# GIfBoardV3.net
KiCad netlist of a schematic drawn in EAGLE
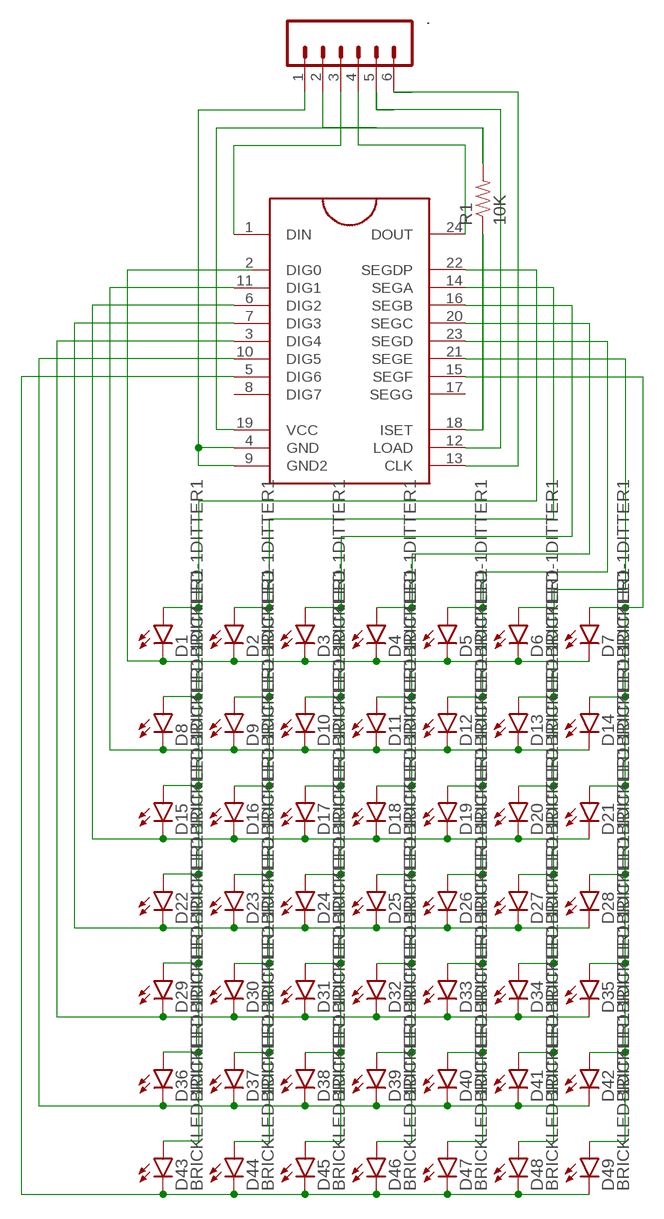
[diagram p0: schematic, sheet 1]

(export (version "E")
  (design (tool "Eeschema 10.0.6"))
  (components
    (comp (ref ".")
      (value "M06NO_SILK_FEMALE_PTH")
      (footprint "eagle-import:1X06_NO_SILK")
      (libsource (lib "eagle-import") (part "M06NO_SILK_FEMALE_PTH"))
    )
    (comp (ref "D1")
      (value "BRICKLED-1DITTER1")
      (footprint "eagle-import:BRICKLED-1DITTER")
      (libsource (lib "eagle-import") (part "BRICKLED-1DITTER1"))
    )
    (comp (ref "D2")
      (value "BRICKLED-1DITTER1")
      (footprint "eagle-import:BRICKLED-1DITTER")
      (libsource (lib "eagle-import") (part "BRICKLED-1DITTER1"))
    )
    (comp (ref "D3")
      (value "BRICKLED-1DITTER1")
      (footprint "eagle-import:BRICKLED-1DITTER")
      (libsource (lib "eagle-import") (part "BRICKLED-1DITTER1"))
    )
    (comp (ref "D4")
      (value "BRICKLED-1DITTER1")
      (footprint "eagle-import:BRICKLED-1DITTER")
      (libsource (lib "eagle-import") (part "BRICKLED-1DITTER1"))
    )
    (comp (ref "D5")
      (value "BRICKLED-1DITTER1")
      (footprint "eagle-import:BRICKLED-1DITTER")
      (libsource (lib "eagle-import") (part "BRICKLED-1DITTER1"))
    )
    (comp (ref "D6")
      (value "BRICKLED-1DITTER1")
      (footprint "eagle-import:BRICKLED-1DITTER")
      (libsource (lib "eagle-import") (part "BRICKLED-1DITTER1"))
    )
    (comp (ref "D7")
      (value "BRICKLED-1DITTER1")
      (footprint "eagle-import:BRICKLED-1DITTER")
      (libsource (lib "eagle-import") (part "BRICKLED-1DITTER1"))
    )
    (comp (ref "D8")
      (value "BRICKLED-1DITTER1")
      (footprint "eagle-import:BRICKLED-1DITTER")
      (libsource (lib "eagle-import") (part "BRICKLED-1DITTER1"))
    )
    (comp (ref "D9")
      (value "BRICKLED-1DITTER1")
      (footprint "eagle-import:BRICKLED-1DITTER")
      (libsource (lib "eagle-import") (part "BRICKLED-1DITTER1"))
    )
    (comp (ref "D10")
      (value "BRICKLED-1DITTER1")
      (footprint "eagle-import:BRICKLED-1DITTER")
      (libsource (lib "eagle-import") (part "BRICKLED-1DITTER1"))
    )
    (comp (ref "D11")
      (value "BRICKLED-1DITTER1")
      (footprint "eagle-import:BRICKLED-1DITTER")
      (libsource (lib "eagle-import") (part "BRICKLED-1DITTER1"))
    )
    (comp (ref "D12")
      (value "BRICKLED-1DITTER1")
      (footprint "eagle-import:BRICKLED-1DITTER")
      (libsource (lib "eagle-import") (part "BRICKLED-1DITTER1"))
    )
    (comp (ref "D13")
      (value "BRICKLED-1DITTER1")
      (footprint "eagle-import:BRICKLED-1DITTER")
      (libsource (lib "eagle-import") (part "BRICKLED-1DITTER1"))
    )
    (comp (ref "D14")
      (value "BRICKLED-1DITTER1")
      (footprint "eagle-import:BRICKLED-1DITTER")
      (libsource (lib "eagle-import") (part "BRICKLED-1DITTER1"))
    )
    (comp (ref "D15")
      (value "BRICKLED-1DITTER1")
      (footprint "eagle-import:BRICKLED-1DITTER")
      (libsource (lib "eagle-import") (part "BRICKLED-1DITTER1"))
    )
    (comp (ref "D16")
      (value "BRICKLED-1DITTER1")
      (footprint "eagle-import:BRICKLED-1DITTER")
      (libsource (lib "eagle-import") (part "BRICKLED-1DITTER1"))
    )
    (comp (ref "D17")
      (value "BRICKLED-1DITTER1")
      (footprint "eagle-import:BRICKLED-1DITTER")
      (libsource (lib "eagle-import") (part "BRICKLED-1DITTER1"))
    )
    (comp (ref "D18")
      (value "BRICKLED-1DITTER1")
      (footprint "eagle-import:BRICKLED-1DITTER")
      (libsource (lib "eagle-import") (part "BRICKLED-1DITTER1"))
    )
    (comp (ref "D19")
      (value "BRICKLED-1DITTER1")
      (footprint "eagle-import:BRICKLED-1DITTER")
      (libsource (lib "eagle-import") (part "BRICKLED-1DITTER1"))
    )
    (comp (ref "D20")
      (value "BRICKLED-1DITTER1")
      (footprint "eagle-import:BRICKLED-1DITTER")
      (libsource (lib "eagle-import") (part "BRICKLED-1DITTER1"))
    )
    (comp (ref "D21")
      (value "BRICKLED-1DITTER1")
      (footprint "eagle-import:BRICKLED-1DITTER")
      (libsource (lib "eagle-import") (part "BRICKLED-1DITTER1"))
    )
    (comp (ref "D22")
      (value "BRICKLED-1DITTER1")
      (footprint "eagle-import:BRICKLED-1DITTER")
      (libsource (lib "eagle-import") (part "BRICKLED-1DITTER1"))
    )
    (comp (ref "D23")
      (value "BRICKLED-1DITTER1")
      (footprint "eagle-import:BRICKLED-1DITTER")
      (libsource (lib "eagle-import") (part "BRICKLED-1DITTER1"))
    )
    (comp (ref "D24")
      (value "BRICKLED-1DITTER1")
      (footprint "eagle-import:BRICKLED-1DITTER")
      (libsource (lib "eagle-import") (part "BRICKLED-1DITTER1"))
    )
    (comp (ref "D25")
      (value "BRICKLED-1DITTER1")
      (footprint "eagle-import:BRICKLED-1DITTER")
      (libsource (lib "eagle-import") (part "BRICKLED-1DITTER1"))
    )
    (comp (ref "D26")
      (value "BRICKLED-1DITTER1")
      (footprint "eagle-import:BRICKLED-1DITTER")
      (libsource (lib "eagle-import") (part "BRICKLED-1DITTER1"))
    )
    (comp (ref "D27")
      (value "BRICKLED-1DITTER1")
      (footprint "eagle-import:BRICKLED-1DITTER")
      (libsource (lib "eagle-import") (part "BRICKLED-1DITTER1"))
    )
    (comp (ref "D28")
      (value "BRICKLED-1DITTER1")
      (footprint "eagle-import:BRICKLED-1DITTER")
      (libsource (lib "eagle-import") (part "BRICKLED-1DITTER1"))
    )
    (comp (ref "D29")
      (value "BRICKLED-1DITTER1")
      (footprint "eagle-import:BRICKLED-1DITTER")
      (libsource (lib "eagle-import") (part "BRICKLED-1DITTER1"))
    )
    (comp (ref "D30")
      (value "BRICKLED-1DITTER1")
      (footprint "eagle-import:BRICKLED-1DITTER")
      (libsource (lib "eagle-import") (part "BRICKLED-1DITTER1"))
    )
    (comp (ref "D31")
      (value "BRICKLED-1DITTER1")
      (footprint "eagle-import:BRICKLED-1DITTER")
      (libsource (lib "eagle-import") (part "BRICKLED-1DITTER1"))
    )
    (comp (ref "D32")
      (value "BRICKLED-1DITTER1")
      (footprint "eagle-import:BRICKLED-1DITTER")
      (libsource (lib "eagle-import") (part "BRICKLED-1DITTER1"))
    )
    (comp (ref "D33")
      (value "BRICKLED-1DITTER1")
      (footprint "eagle-import:BRICKLED-1DITTER")
      (libsource (lib "eagle-import") (part "BRICKLED-1DITTER1"))
    )
    (comp (ref "D34")
      (value "BRICKLED-1DITTER1")
      (footprint "eagle-import:BRICKLED-1DITTER")
      (libsource (lib "eagle-import") (part "BRICKLED-1DITTER1"))
    )
    (comp (ref "D35")
      (value "BRICKLED-1DITTER1")
      (footprint "eagle-import:BRICKLED-1DITTER")
      (libsource (lib "eagle-import") (part "BRICKLED-1DITTER1"))
    )
    (comp (ref "D36")
      (value "BRICKLED-1DITTER1")
      (footprint "eagle-import:BRICKLED-1DITTER")
      (libsource (lib "eagle-import") (part "BRICKLED-1DITTER1"))
    )
    (comp (ref "D37")
      (value "BRICKLED-1DITTER1")
      (footprint "eagle-import:BRICKLED-1DITTER")
      (libsource (lib "eagle-import") (part "BRICKLED-1DITTER1"))
    )
    (comp (ref "D38")
      (value "BRICKLED-1DITTER1")
      (footprint "eagle-import:BRICKLED-1DITTER")
      (libsource (lib "eagle-import") (part "BRICKLED-1DITTER1"))
    )
    (comp (ref "D39")
      (value "BRICKLED-1DITTER1")
      (footprint "eagle-import:BRICKLED-1DITTER")
      (libsource (lib "eagle-import") (part "BRICKLED-1DITTER1"))
    )
    (comp (ref "D40")
      (value "BRICKLED-1DITTER1")
      (footprint "eagle-import:BRICKLED-1DITTER")
      (libsource (lib "eagle-import") (part "BRICKLED-1DITTER1"))
    )
    (comp (ref "D41")
      (value "BRICKLED-1DITTER1")
      (footprint "eagle-import:BRICKLED-1DITTER")
      (libsource (lib "eagle-import") (part "BRICKLED-1DITTER1"))
    )
    (comp (ref "D42")
      (value "BRICKLED-1DITTER1")
      (footprint "eagle-import:BRICKLED-1DITTER")
      (libsource (lib "eagle-import") (part "BRICKLED-1DITTER1"))
    )
    (comp (ref "D43")
      (value "BRICKLED-1DITTER1")
      (footprint "eagle-import:BRICKLED-1DITTER")
      (libsource (lib "eagle-import") (part "BRICKLED-1DITTER1"))
    )
    (comp (ref "D44")
      (value "BRICKLED-1DITTER1")
      (footprint "eagle-import:BRICKLED-1DITTER")
      (libsource (lib "eagle-import") (part "BRICKLED-1DITTER1"))
    )
    (comp (ref "D45")
      (value "BRICKLED-1DITTER1")
      (footprint "eagle-import:BRICKLED-1DITTER")
      (libsource (lib "eagle-import") (part "BRICKLED-1DITTER1"))
    )
    (comp (ref "D46")
      (value "BRICKLED-1DITTER1")
      (footprint "eagle-import:BRICKLED-1DITTER")
      (libsource (lib "eagle-import") (part "BRICKLED-1DITTER1"))
    )
    (comp (ref "D47")
      (value "BRICKLED-1DITTER1")
      (footprint "eagle-import:BRICKLED-1DITTER")
      (libsource (lib "eagle-import") (part "BRICKLED-1DITTER1"))
    )
    (comp (ref "D48")
      (value "BRICKLED-1DITTER1")
      (footprint "eagle-import:BRICKLED-1DITTER")
      (libsource (lib "eagle-import") (part "BRICKLED-1DITTER1"))
    )
    (comp (ref "D49")
      (value "BRICKLED-1DITTER1")
      (footprint "eagle-import:BRICKLED-1DITTER")
      (libsource (lib "eagle-import") (part "BRICKLED-1DITTER1"))
    )
    (comp (ref "MAX7219")
      (value "MAX7219DIP")
      (footprint "eagle-import:DIL24")
      (libsource (lib "eagle-import") (part "MAX7219DIP"))
    )
    (comp (ref "R1")
      (value "10K")
      (footprint "eagle-import:AXIAL-0.3")
      (libsource (lib "eagle-import") (part "1KOHM-1/4W-5%(PTH)"))
    )
  )
  (nets
    (net (code "1") (name "Net-(D1-C)") (class "Default")
      (node (ref "D1") (pin "K") (pinfunction "C_K") (pintype "passive"))
      (node (ref "D2") (pin "K") (pinfunction "C_K") (pintype "passive"))
      (node (ref "D3") (pin "K") (pinfunction "C_K") (pintype "passive"))
      (node (ref "D4") (pin "K") (pinfunction "C_K") (pintype "passive"))
      (node (ref "D5") (pin "K") (pinfunction "C_K") (pintype "passive"))
      (node (ref "D6") (pin "K") (pinfunction "C_K") (pintype "passive"))
      (node (ref "D7") (pin "K") (pinfunction "C_K") (pintype "passive"))
    )
    (net (code "2") (name "Net-(D10-C)") (class "Default")
      (node (ref "D10") (pin "K") (pinfunction "C_K") (pintype "passive"))
      (node (ref "D11") (pin "K") (pinfunction "C_K") (pintype "passive"))
      (node (ref "D12") (pin "K") (pinfunction "C_K") (pintype "passive"))
      (node (ref "D13") (pin "K") (pinfunction "C_K") (pintype "passive"))
      (node (ref "D14") (pin "K") (pinfunction "C_K") (pintype "passive"))
      (node (ref "D8") (pin "K") (pinfunction "C_K") (pintype "passive"))
      (node (ref "D9") (pin "K") (pinfunction "C_K") (pintype "passive"))
      (node (ref "MAX7219") (pin "11") (pinfunction "DIG1_11") (pintype "bidirectional"))
    )
    (net (code "3") (name "Net-(D15-C)") (class "Default")
      (node (ref "D15") (pin "K") (pinfunction "C_K") (pintype "passive"))
      (node (ref "D16") (pin "K") (pinfunction "C_K") (pintype "passive"))
      (node (ref "D17") (pin "K") (pinfunction "C_K") (pintype "passive"))
      (node (ref "D18") (pin "K") (pinfunction "C_K") (pintype "passive"))
      (node (ref "D19") (pin "K") (pinfunction "C_K") (pintype "passive"))
      (node (ref "D20") (pin "K") (pinfunction "C_K") (pintype "passive"))
      (node (ref "D21") (pin "K") (pinfunction "C_K") (pintype "passive"))
      (node (ref "MAX7219") (pin "6") (pinfunction "DIG2_6") (pintype "bidirectional"))
    )
    (net (code "4") (name "Net-(D22-C)") (class "Default")
      (node (ref "D22") (pin "K") (pinfunction "C_K") (pintype "passive"))
      (node (ref "D23") (pin "K") (pinfunction "C_K") (pintype "passive"))
      (node (ref "D24") (pin "K") (pinfunction "C_K") (pintype "passive"))
      (node (ref "D25") (pin "K") (pinfunction "C_K") (pintype "passive"))
      (node (ref "D26") (pin "K") (pinfunction "C_K") (pintype "passive"))
      (node (ref "D27") (pin "K") (pinfunction "C_K") (pintype "passive"))
      (node (ref "D28") (pin "K") (pinfunction "C_K") (pintype "passive"))
      (node (ref "MAX7219") (pin "7") (pinfunction "DIG3_7") (pintype "bidirectional"))
    )
    (net (code "5") (name "Net-(D29-C)") (class "Default")
      (node (ref "D29") (pin "K") (pinfunction "C_K") (pintype "passive"))
      (node (ref "D30") (pin "K") (pinfunction "C_K") (pintype "passive"))
      (node (ref "D31") (pin "K") (pinfunction "C_K") (pintype "passive"))
      (node (ref "D32") (pin "K") (pinfunction "C_K") (pintype "passive"))
      (node (ref "D33") (pin "K") (pinfunction "C_K") (pintype "passive"))
      (node (ref "D34") (pin "K") (pinfunction "C_K") (pintype "passive"))
      (node (ref "D35") (pin "K") (pinfunction "C_K") (pintype "passive"))
      (node (ref "MAX7219") (pin "3") (pinfunction "DIG4_3") (pintype "bidirectional"))
    )
    (net (code "6") (name "Net-(D36-C)") (class "Default")
      (node (ref "D36") (pin "K") (pinfunction "C_K") (pintype "passive"))
      (node (ref "D37") (pin "K") (pinfunction "C_K") (pintype "passive"))
      (node (ref "D38") (pin "K") (pinfunction "C_K") (pintype "passive"))
      (node (ref "D39") (pin "K") (pinfunction "C_K") (pintype "passive"))
      (node (ref "D40") (pin "K") (pinfunction "C_K") (pintype "passive"))
      (node (ref "D41") (pin "K") (pinfunction "C_K") (pintype "passive"))
      (node (ref "D42") (pin "K") (pinfunction "C_K") (pintype "passive"))
      (node (ref "MAX7219") (pin "10") (pinfunction "DIG5_10") (pintype "bidirectional"))
    )
    (net (code "7") (name "Net-(D43-C)") (class "Default")
      (node (ref "D43") (pin "K") (pinfunction "C_K") (pintype "passive"))
      (node (ref "D44") (pin "K") (pinfunction "C_K") (pintype "passive"))
      (node (ref "D45") (pin "K") (pinfunction "C_K") (pintype "passive"))
      (node (ref "D46") (pin "K") (pinfunction "C_K") (pintype "passive"))
      (node (ref "D47") (pin "K") (pinfunction "C_K") (pintype "passive"))
      (node (ref "D48") (pin "K") (pinfunction "C_K") (pintype "passive"))
      (node (ref "D49") (pin "K") (pinfunction "C_K") (pintype "passive"))
      (node (ref "MAX7219") (pin "5") (pinfunction "DIG6_5") (pintype "bidirectional"))
    )
    (net (code "8") (name "Net-(MAX7219-CLK)") (class "Default")
      (node (ref ".") (pin "6") (pinfunction "6_6") (pintype "passive"))
      (node (ref "MAX7219") (pin "13") (pinfunction "CLK_13") (pintype "bidirectional"))
    )
    (net (code "9") (name "Net-(MAX7219-DIN)") (class "Default")
      (node (ref ".") (pin "3") (pinfunction "3_3") (pintype "passive"))
      (node (ref "MAX7219") (pin "1") (pinfunction "DIN_1") (pintype "bidirectional"))
    )
    (net (code "10") (name "Net-(MAX7219-DOUT)") (class "Default")
      (node (ref ".") (pin "4") (pinfunction "4_4") (pintype "passive"))
      (node (ref "MAX7219") (pin "24") (pinfunction "DOUT_24") (pintype "bidirectional"))
    )
    (net (code "11") (name "Net-(MAX7219-GND)") (class "Default")
      (node (ref ".") (pin "1") (pinfunction "1_1") (pintype "passive"))
      (node (ref "MAX7219") (pin "4") (pinfunction "GND_4") (pintype "bidirectional"))
      (node (ref "MAX7219") (pin "9") (pinfunction "GND2_9") (pintype "bidirectional"))
    )
    (net (code "12") (name "Net-(MAX7219-ISET)") (class "Default")
      (node (ref "MAX7219") (pin "18") (pinfunction "ISET_18") (pintype "bidirectional"))
      (node (ref "R1") (pin "P$1") (pinfunction "1_P$1") (pintype "passive"))
    )
    (net (code "13") (name "Net-(MAX7219-LOAD)") (class "Default")
      (node (ref ".") (pin "5") (pinfunction "5_5") (pintype "passive"))
      (node (ref "MAX7219") (pin "12") (pinfunction "LOAD_12") (pintype "bidirectional"))
    )
    (net (code "14") (name "Net-(MAX7219-SEGA)") (class "Default")
      (node (ref "D16") (pin "A") (pinfunction "A_A") (pintype "passive"))
      (node (ref "D2") (pin "A") (pinfunction "A_A") (pintype "passive"))
      (node (ref "D23") (pin "A") (pinfunction "A_A") (pintype "passive"))
      (node (ref "D30") (pin "A") (pinfunction "A_A") (pintype "passive"))
      (node (ref "D37") (pin "A") (pinfunction "A_A") (pintype "passive"))
      (node (ref "D44") (pin "A") (pinfunction "A_A") (pintype "passive"))
      (node (ref "D9") (pin "A") (pinfunction "A_A") (pintype "passive"))
      (node (ref "MAX7219") (pin "14") (pinfunction "SEGA_14") (pintype "bidirectional"))
    )
    (net (code "15") (name "Net-(MAX7219-SEGB)") (class "Default")
      (node (ref "D10") (pin "A") (pinfunction "A_A") (pintype "passive"))
      (node (ref "D17") (pin "A") (pinfunction "A_A") (pintype "passive"))
      (node (ref "D24") (pin "A") (pinfunction "A_A") (pintype "passive"))
      (node (ref "D3") (pin "A") (pinfunction "A_A") (pintype "passive"))
      (node (ref "D31") (pin "A") (pinfunction "A_A") (pintype "passive"))
      (node (ref "D38") (pin "A") (pinfunction "A_A") (pintype "passive"))
      (node (ref "D45") (pin "A") (pinfunction "A_A") (pintype "passive"))
      (node (ref "MAX7219") (pin "16") (pinfunction "SEGB_16") (pintype "bidirectional"))
    )
    (net (code "16") (name "Net-(MAX7219-SEGC)") (class "Default")
      (node (ref "D11") (pin "A") (pinfunction "A_A") (pintype "passive"))
      (node (ref "D18") (pin "A") (pinfunction "A_A") (pintype "passive"))
      (node (ref "D25") (pin "A") (pinfunction "A_A") (pintype "passive"))
      (node (ref "D32") (pin "A") (pinfunction "A_A") (pintype "passive"))
      (node (ref "D39") (pin "A") (pinfunction "A_A") (pintype "passive"))
      (node (ref "D4") (pin "A") (pinfunction "A_A") (pintype "passive"))
      (node (ref "D46") (pin "A") (pinfunction "A_A") (pintype "passive"))
      (node (ref "MAX7219") (pin "20") (pinfunction "SEGC_20") (pintype "bidirectional"))
    )
    (net (code "17") (name "Net-(MAX7219-SEGD)") (class "Default")
      (node (ref "D12") (pin "A") (pinfunction "A_A") (pintype "passive"))
      (node (ref "D19") (pin "A") (pinfunction "A_A") (pintype "passive"))
      (node (ref "D26") (pin "A") (pinfunction "A_A") (pintype "passive"))
      (node (ref "D33") (pin "A") (pinfunction "A_A") (pintype "passive"))
      (node (ref "D40") (pin "A") (pinfunction "A_A") (pintype "passive"))
      (node (ref "D47") (pin "A") (pinfunction "A_A") (pintype "passive"))
      (node (ref "D5") (pin "A") (pinfunction "A_A") (pintype "passive"))
      (node (ref "MAX7219") (pin "23") (pinfunction "SEGD_23") (pintype "bidirectional"))
    )
    (net (code "18") (name "Net-(MAX7219-SEGDP)") (class "Default")
      (node (ref "D1") (pin "A") (pinfunction "A_A") (pintype "passive"))
      (node (ref "D15") (pin "A") (pinfunction "A_A") (pintype "passive"))
      (node (ref "D22") (pin "A") (pinfunction "A_A") (pintype "passive"))
      (node (ref "D29") (pin "A") (pinfunction "A_A") (pintype "passive"))
      (node (ref "D36") (pin "A") (pinfunction "A_A") (pintype "passive"))
      (node (ref "D43") (pin "A") (pinfunction "A_A") (pintype "passive"))
      (node (ref "D8") (pin "A") (pinfunction "A_A") (pintype "passive"))
      (node (ref "MAX7219") (pin "22") (pinfunction "SEGDP_22") (pintype "bidirectional"))
    )
    (net (code "19") (name "Net-(MAX7219-SEGE)") (class "Default")
      (node (ref "D13") (pin "A") (pinfunction "A_A") (pintype "passive"))
      (node (ref "D20") (pin "A") (pinfunction "A_A") (pintype "passive"))
      (node (ref "D27") (pin "A") (pinfunction "A_A") (pintype "passive"))
      (node (ref "D34") (pin "A") (pinfunction "A_A") (pintype "passive"))
      (node (ref "D41") (pin "A") (pinfunction "A_A") (pintype "passive"))
      (node (ref "D48") (pin "A") (pinfunction "A_A") (pintype "passive"))
      (node (ref "D6") (pin "A") (pinfunction "A_A") (pintype "passive"))
      (node (ref "MAX7219") (pin "21") (pinfunction "SEGE_21") (pintype "bidirectional"))
    )
    (net (code "20") (name "Net-(MAX7219-SEGF)") (class "Default")
      (node (ref "D14") (pin "A") (pinfunction "A_A") (pintype "passive"))
      (node (ref "D21") (pin "A") (pinfunction "A_A") (pintype "passive"))
      (node (ref "D28") (pin "A") (pinfunction "A_A") (pintype "passive"))
      (node (ref "D35") (pin "A") (pinfunction "A_A") (pintype "passive"))
      (node (ref "D42") (pin "A") (pinfunction "A_A") (pintype "passive"))
      (node (ref "D49") (pin "A") (pinfunction "A_A") (pintype "passive"))
      (node (ref "D7") (pin "A") (pinfunction "A_A") (pintype "passive"))
      (node (ref "MAX7219") (pin "15") (pinfunction "SEGF_15") (pintype "bidirectional"))
    )
    (net (code "21") (name "Net-(MAX7219-VCC)") (class "Default")
      (node (ref ".") (pin "2") (pinfunction "2_2") (pintype "passive"))
      (node (ref "MAX7219") (pin "19") (pinfunction "VCC_19") (pintype "bidirectional"))
      (node (ref "R1") (pin "P$2") (pinfunction "2_P$2") (pintype "passive"))
    )
    (net (code "22") (name "unconnected-(MAX7219-DIG0-Pad2)") (class "Default")
      (node (ref "MAX7219") (pin "2") (pinfunction "DIG0_2") (pintype "bidirectional"))
    )
    (net (code "23") (name "unconnected-(MAX7219-DIG7-Pad8)") (class "Default")
      (node (ref "MAX7219") (pin "8") (pinfunction "DIG7_8") (pintype "bidirectional"))
    )
    (net (code "24") (name "unconnected-(MAX7219-SEGG-Pad17)") (class "Default")
      (node (ref "MAX7219") (pin "17") (pinfunction "SEGG_17") (pintype "bidirectional"))
    )
  )
)
